# Power.net
KiCad netlist of a schematic drawn in Altium Designer
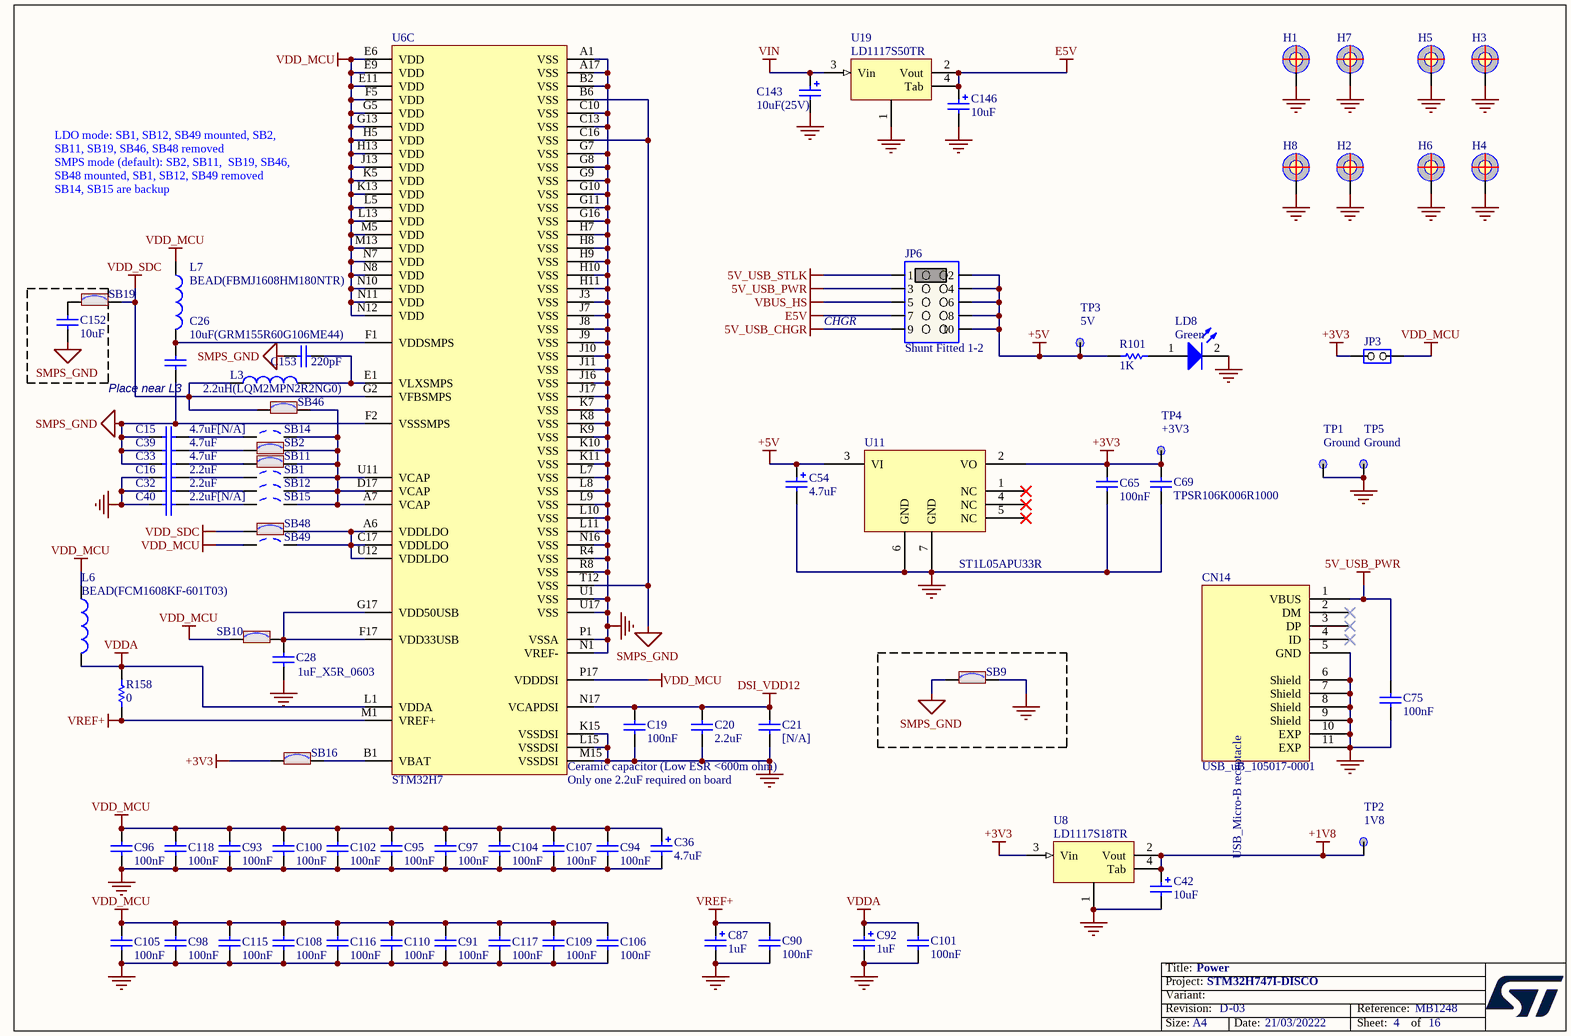
[diagram p0: Power.SchDoc]

(export (version "E")
  (design (tool "Eeschema 10.0.6"))
  (components
    (comp (ref "C15")
      (value "4.7uF[N/A]")
      (footprint "0402C")
      (description "Capacitor")
      (fields (field (name "PUBLISHER") "Altium Limited"))
      (libsource (lib "Miscellaneous Devices") (part "cap"))
    )
    (comp (ref "C16")
      (value "2.2uF")
      (footprint "0603C")
      (description "Capacitor")
      (fields (field (name "PUBLISHER") "Altium Limited"))
      (libsource (lib "Miscellaneous Devices") (part "Cap"))
    )
    (comp (ref "C19")
      (value "100nF")
      (footprint "0402C")
      (description "Capacitor")
      (fields (field (name "PUBLISHER") "Altium Limited"))
      (libsource (lib "Miscellaneous Devices") (part "CAP"))
    )
    (comp (ref "C20")
      (value "2.2uF")
      (footprint "0603C")
      (description "Capacitor")
      (fields (field (name "PUBLISHER") "Altium Limited"))
      (libsource (lib "Miscellaneous Devices") (part "CAP"))
    )
    (comp (ref "C21")
      (value "[N/A]")
      (footprint "1206C")
      (description "Capacitor")
      (fields (field (name "PUBLISHER") "Altium Limited"))
      (libsource (lib "Miscellaneous Devices") (part "cap"))
    )
    (comp (ref "C26")
      (value "10uF(GRM155R60G106ME44)")
      (footprint "0402C")
      (description "Capacitor")
      (fields (field (name "PUBLISHER") "Altium Limited"))
      (libsource (lib "Miscellaneous Devices") (part "Cap"))
    )
    (comp (ref "C28")
      (value "1uF_X5R_0603")
      (footprint "0603C")
      (description "0603  X5R 1礔")
      (fields (field (name "TOLERANCE") "10%"))
      (libsource (lib "MB963_1") (part "CAP SMD 0603  X5R 1礔 25V 10%"))
    )
    (comp (ref "C32")
      (value "2.2uF")
      (footprint "0603C")
      (description "Capacitor")
      (fields (field (name "PUBLISHER") "Altium Limited"))
      (libsource (lib "Miscellaneous Devices") (part "Cap"))
    )
    (comp (ref "C33")
      (value "4.7uF")
      (footprint "0402C")
      (description "Capacitor")
      (fields (field (name "PUBLISHER") "Altium Limited"))
      (libsource (lib "Miscellaneous Devices") (part "Cap"))
    )
    (comp (ref "C36")
      (value "4.7uF")
      (footprint "TAN-A")
      (description "Polarized Capacitor (Radial)")
      (fields (field (name "PUBLISHER") "Altium Limited"))
      (libsource (lib "Miscellaneous Devices") (part "Cap Pol1"))
    )
    (comp (ref "C39")
      (value "4.7uF")
      (footprint "0402C")
      (description "Capacitor")
      (fields (field (name "PUBLISHER") "Altium Limited"))
      (libsource (lib "Miscellaneous Devices") (part "Cap"))
    )
    (comp (ref "C40")
      (value "2.2uF[N/A]")
      (footprint "0603C")
      (description "Capacitor")
      (fields (field (name "PUBLISHER") "Altium Limited"))
      (libsource (lib "Miscellaneous Devices") (part "Cap"))
    )
    (comp (ref "C42")
      (value "10uF")
      (footprint "TAN-A")
      (description "Polarized Capacitor,10uF,10V,10%,typeA,VISHAY")
      (libsource (lib "MCD_TOOLS") (part "Cap_10uF_POL_10%_TANA"))
    )
    (comp (ref "C54")
      (value "4.7uF")
      (footprint "TAN-A")
      (description "Polarized Capacitor (Radial)")
      (fields (field (name "PUBLISHER") "Altium Limited"))
      (libsource (lib "*") (part "Cap Pol1"))
    )
    (comp (ref "C65")
      (value "100nF")
      (footprint "0603C")
      (description "Capacitor")
      (fields (field (name "PUBLISHER") "Altium Limited"))
      (libsource (lib "Miscellaneous Devices") (part "Cap"))
    )
    (comp (ref "C69")
      (value "TPSR106K006R1000")
      (footprint "0805C")
      (description "Capacitor")
      (libsource (lib "Miscellaneous Devices") (part "Cap"))
    )
    (comp (ref "C75")
      (value "100nF")
      (footprint "0402C")
      (description "Capacitor,20pF,50V,NPO,5%,0402")
      (fields
        (field (name "INTERNAL_PART_NUMBER") "MCD-00016")
        (field (name "MANUFACTURER_PART_NUMBER") "CC0402JRNPO9BN200")
        (field (name "PROVIDED_BY") "Subcon")
      )
      (libsource (lib "MCD_PARTS_database") (part "Capacitor"))
    )
    (comp (ref "C87")
      (value "1uF")
      (footprint "TAN-A")
      (description "Polarized Capacitor (Radial)")
      (fields (field (name "PUBLISHER") "Altium Limited"))
      (libsource (lib "Miscellaneous Devices") (part "Cap Pol1"))
    )
    (comp (ref "C90")
      (value "100nF")
      (footprint "0402C")
      (description "Capacitor")
      (fields (field (name "PUBLISHER") "Altium Limited"))
      (libsource (lib "Miscellaneous Devices") (part "Cap"))
    )
    (comp (ref "C91")
      (value "100nF")
      (footprint "0402C")
      (description "Capacitor")
      (fields (field (name "PUBLISHER") "Altium Limited"))
      (libsource (lib "Miscellaneous Devices") (part "CAP"))
    )
    (comp (ref "C92")
      (value "1uF")
      (footprint "TAN-A")
      (description "Polarized Capacitor (Radial)")
      (fields (field (name "PUBLISHER") "Altium Limited"))
      (libsource (lib "Miscellaneous Devices") (part "Cap Pol1"))
    )
    (comp (ref "C93")
      (value "100nF")
      (footprint "0402C")
      (description "Capacitor")
      (fields (field (name "PUBLISHER") "Altium Limited"))
      (libsource (lib "Miscellaneous Devices") (part "CAP"))
    )
    (comp (ref "C94")
      (value "100nF")
      (footprint "0402C")
      (description "Capacitor")
      (fields (field (name "PUBLISHER") "Altium Limited"))
      (libsource (lib "Miscellaneous Devices") (part "CAP"))
    )
    (comp (ref "C95")
      (value "100nF")
      (footprint "0402C")
      (description "Capacitor")
      (fields (field (name "PUBLISHER") "Altium Limited"))
      (libsource (lib "Miscellaneous Devices") (part "CAP"))
    )
    (comp (ref "C96")
      (value "100nF")
      (footprint "0402C")
      (description "Capacitor")
      (fields (field (name "PUBLISHER") "Altium Limited"))
      (libsource (lib "Miscellaneous Devices") (part "CAP"))
    )
    (comp (ref "C97")
      (value "100nF")
      (footprint "0402C")
      (description "Capacitor")
      (fields (field (name "PUBLISHER") "Altium Limited"))
      (libsource (lib "Miscellaneous Devices") (part "CAP"))
    )
    (comp (ref "C98")
      (value "100nF")
      (footprint "0402C")
      (description "Capacitor")
      (fields (field (name "PUBLISHER") "Altium Limited"))
      (libsource (lib "Miscellaneous Devices") (part "CAP"))
    )
    (comp (ref "C100")
      (value "100nF")
      (footprint "0402C")
      (description "Capacitor")
      (fields (field (name "PUBLISHER") "Altium Limited"))
      (libsource (lib "Miscellaneous Devices") (part "CAP"))
    )
    (comp (ref "C101")
      (value "100nF")
      (footprint "0402C")
      (description "Capacitor")
      (fields (field (name "PUBLISHER") "Altium Limited"))
      (libsource (lib "Miscellaneous Devices") (part "Cap"))
    )
    (comp (ref "C102")
      (value "100nF")
      (footprint "0402C")
      (description "Capacitor")
      (fields (field (name "PUBLISHER") "Altium Limited"))
      (libsource (lib "Miscellaneous Devices") (part "CAP"))
    )
    (comp (ref "C104")
      (value "100nF")
      (footprint "0402C")
      (description "Capacitor")
      (fields (field (name "PUBLISHER") "Altium Limited"))
      (libsource (lib "Miscellaneous Devices") (part "CAP"))
    )
    (comp (ref "C105")
      (value "100nF")
      (footprint "0402C")
      (description "Capacitor")
      (fields (field (name "PUBLISHER") "Altium Limited"))
      (libsource (lib "Miscellaneous Devices") (part "CAP"))
    )
    (comp (ref "C106")
      (value "100nF")
      (footprint "0402C")
      (description "Capacitor")
      (fields (field (name "PUBLISHER") "Altium Limited"))
      (libsource (lib "Miscellaneous Devices") (part "CAP"))
    )
    (comp (ref "C107")
      (value "100nF")
      (footprint "0402C")
      (description "Capacitor")
      (fields (field (name "PUBLISHER") "Altium Limited"))
      (libsource (lib "Miscellaneous Devices") (part "CAP"))
    )
    (comp (ref "C108")
      (value "100nF")
      (footprint "0402C")
      (description "Capacitor")
      (fields (field (name "PUBLISHER") "Altium Limited"))
      (libsource (lib "Miscellaneous Devices") (part "CAP"))
    )
    (comp (ref "C109")
      (value "100nF")
      (footprint "0402C")
      (description "Capacitor")
      (fields (field (name "PUBLISHER") "Altium Limited"))
      (libsource (lib "Miscellaneous Devices") (part "CAP"))
    )
    (comp (ref "C110")
      (value "100nF")
      (footprint "0402C")
      (description "Capacitor")
      (fields (field (name "PUBLISHER") "Altium Limited"))
      (libsource (lib "Miscellaneous Devices") (part "CAP"))
    )
    (comp (ref "C115")
      (value "100nF")
      (footprint "0402C")
      (description "Capacitor")
      (fields (field (name "PUBLISHER") "Altium Limited"))
      (libsource (lib "Miscellaneous Devices") (part "CAP"))
    )
    (comp (ref "C116")
      (value "100nF")
      (footprint "0402C")
      (description "Capacitor")
      (fields (field (name "PUBLISHER") "Altium Limited"))
      (libsource (lib "Miscellaneous Devices") (part "CAP"))
    )
    (comp (ref "C117")
      (value "100nF")
      (footprint "0402C")
      (description "Capacitor")
      (fields (field (name "PUBLISHER") "Altium Limited"))
      (libsource (lib "Miscellaneous Devices") (part "CAP"))
    )
    (comp (ref "C118")
      (value "100nF")
      (footprint "0402C")
      (description "Capacitor")
      (fields (field (name "PUBLISHER") "Altium Limited"))
      (libsource (lib "Miscellaneous Devices") (part "CAP"))
    )
    (comp (ref "C143")
      (value "10uF(25V)")
      (footprint "TAN-B")
      (description "Polarized Capacitor (Radial)")
      (fields (field (name "PUBLISHER") "Altium Limited"))
      (libsource (lib "Miscellaneous Devices") (part "Cap Pol1"))
    )
    (comp (ref "C146")
      (value "10uF")
      (footprint "TAN-A")
      (description "Polarized Capacitor,10uF,10V,10%,typeA,VISHAY")
      (libsource (lib "MCD_TOOLS") (part "Cap_10uF_POL_10%_TANA"))
    )
    (comp (ref "C152")
      (value "10uF")
      (footprint "0603C")
      (description "Capacitor")
      (fields (field (name "PUBLISHER") "Altium Limited"))
      (libsource (lib "Miscellaneous Devices") (part "Cap"))
    )
    (comp (ref "C153")
      (value "220pF")
      (footprint "0402C")
      (description "Capacitor")
      (fields (field (name "PUBLISHER") "Altium Limited"))
      (libsource (lib "Miscellaneous Devices") (part "Cap"))
    )
    (comp (ref "CN14")
      (value "USB_uB_105017-0001")
      (footprint "MICRO_USB_B_105017")
      (description "USB-MICRO-B, 0.65mm, RA, SMT, Bottom Mount,")
      (fields
        (field (name "INTERNAL_PART_NUMBER") "MCD-00028")
        (field (name "MANUFACTURER_PART_NUMBER") "1050170001")
        (field (name "PROVIDED_BY") "Subcon")
      )
      (libsource (lib "MCD_PARTS_database") (part "USB_uB_105017.0001"))
    )
    (comp (ref "H1")
      (value "POSITION HOLE C6D3R5")
      (footprint "HOLE_C7D3R5")
      (libsource (lib "MCD_TOOLS_MISCELLANEOUS") (part "POSITION HOLE C6D3R5"))
    )
    (comp (ref "H2")
      (value "POSITION HOLE C6D3R5")
      (footprint "HOLE_C7D3R5")
      (libsource (lib "MCD_TOOLS_MISCELLANEOUS") (part "POSITION HOLE C6D3R5"))
    )
    (comp (ref "H3")
      (value "POSITION HOLE C6D3R5")
      (footprint "HOLE_C9D4R5")
      (libsource (lib "MCD_TOOLS_MISCELLANEOUS") (part "POSITION HOLE C6D3R5"))
    )
    (comp (ref "H4")
      (value "POSITION HOLE C6D3R5")
      (footprint "HOLE_C9D4R5")
      (libsource (lib "MCD_TOOLS_MISCELLANEOUS") (part "POSITION HOLE C6D3R5"))
    )
    (comp (ref "H5")
      (value "POSITION HOLE C6D3R5")
      (footprint "HOLE_C9D4R5")
      (libsource (lib "MCD_TOOLS_MISCELLANEOUS") (part "POSITION HOLE C6D3R5"))
    )
    (comp (ref "H6")
      (value "POSITION HOLE C6D3R5")
      (footprint "HOLE_C9D4R5")
      (libsource (lib "MCD_TOOLS_MISCELLANEOUS") (part "POSITION HOLE C6D3R5"))
    )
    (comp (ref "H7")
      (value "POSITION HOLE C6D3R5")
      (footprint "HOLE_C7D3R5")
      (libsource (lib "MCD_TOOLS_MISCELLANEOUS") (part "POSITION HOLE C6D3R5"))
    )
    (comp (ref "H8")
      (value "POSITION HOLE C6D3R5")
      (footprint "HOLE_C7D3R5")
      (libsource (lib "MCD_TOOLS_MISCELLANEOUS") (part "POSITION HOLE C6D3R5"))
    )
    (comp (ref "JP3") (value "~") (footprint "SIP2") (libsource (lib "*") (part "JP2")))
    (comp (ref "JP6")
      (value "Shunt Fitted 1-2")
      (footprint "HDR_2X5_2R54")
      (description "Header, 5x2, 2,54mm, VR, TH, Height 5.84mm/2.54mm - Shunt Fitted 1-2")
      (fields
        (field (name "INTERNAL_PART_NUMBER") "MCD-01203")
        (field (name "MANUFACTURER_PART_NUMBER") "TSW-105-07-x-D")
        (field (name "PROVIDED_BY") "Subcon")
      )
      (libsource (lib "MCD_PARTS_database") (part "Jumper_Header 5x2 Fitted 1-2"))
    )
    (comp (ref "L3")
      (value "2.2uH(LQM2MPN2R2NG0)")
      (footprint "LSM2_VLS2016E_S")
      (description "Inductor")
      (fields (field (name "PUBLISHER") "Altium Limited"))
      (libsource (lib "Miscellaneous Devices") (part "Inductor"))
    )
    (comp (ref "L6")
      (value "BEAD(FCM1608KF-601T03)")
      (footprint "0603L")
      (description "Inductor")
      (fields (field (name "PUBLISHER") "Altium Limited"))
      (libsource (lib "Miscellaneous Devices") (part "Inductor"))
    )
    (comp (ref "L7")
      (value "BEAD(FBMJ1608HM180NTR)")
      (footprint "0603L")
      (description "Inductor")
      (fields (field (name "PUBLISHER") "Altium Limited"))
      (libsource (lib "Miscellaneous Devices") (part "Inductor"))
    )
    (comp (ref "LD8")
      (value "Green")
      (footprint "0603D")
      (description "Typical RED, GREEN, YELLOW, AMBER GaAs LED")
      (fields (field (name "PUBLISHER") "Altium Limited"))
      (libsource (lib "Miscellaneous Devices") (part "LED2"))
    )
    (comp (ref "R101")
      (value "1K")
      (footprint "0603R")
      (description "Resistor")
      (fields (field (name "PUBLISHER") "Altium Limited"))
      (libsource (lib "Miscellaneous Devices") (part "res1"))
    )
    (comp (ref "R158")
      (value "0")
      (footprint "0603R")
      (description "Resistor")
      (fields (field (name "PUBLISHER") "Altium Limited"))
      (libsource (lib "Miscellaneous Devices") (part "Res1"))
    )
    (comp (ref "SB1")
      (value "Solder Bridge OFF")
      (footprint "SB_0603")
      (libsource (lib "MCD_TOOLS") (part "SB_OFF"))
    )
    (comp (ref "SB2")
      (value "Solder Bridge ON")
      (footprint "SB_0603")
      (libsource (lib "MCD_TOOLS") (part "SB_ON"))
    )
    (comp (ref "SB9")
      (value "Solder Bridge ON")
      (footprint "SB_0603")
      (libsource (lib "MCD_TOOLS") (part "SB_ON"))
    )
    (comp (ref "SB10")
      (value "Solder Bridge ON")
      (footprint "SB_0603")
      (libsource (lib "MCD_TOOLS") (part "SB_ON"))
    )
    (comp (ref "SB11")
      (value "Solder Bridge ON")
      (footprint "SB_0603")
      (libsource (lib "MCD_TOOLS") (part "SB_ON"))
    )
    (comp (ref "SB12")
      (value "Solder Bridge OFF")
      (footprint "SB_0603")
      (libsource (lib "MCD_TOOLS") (part "SB_OFF"))
    )
    (comp (ref "SB14")
      (value "Solder Bridge OFF")
      (footprint "SB_0603")
      (libsource (lib "MCD_TOOLS") (part "SB_OFF"))
    )
    (comp (ref "SB15")
      (value "Solder Bridge OFF")
      (footprint "SB_0603")
      (libsource (lib "MCD_TOOLS") (part "SB_OFF"))
    )
    (comp (ref "SB16")
      (value "Solder Bridge ON")
      (footprint "SB_0603")
      (libsource (lib "MCD_TOOLS") (part "SB_ON"))
    )
    (comp (ref "SB19")
      (value "Solder Bridge ON")
      (footprint "SB_0603")
      (libsource (lib "MCD_TOOLS") (part "SB_ON"))
    )
    (comp (ref "SB46")
      (value "Solder Bridge ON")
      (footprint "SB_0603")
      (libsource (lib "MCD_TOOLS") (part "SB_ON"))
    )
    (comp (ref "SB48")
      (value "Solder Bridge ON")
      (footprint "SB_0603")
      (libsource (lib "MCD_TOOLS") (part "SB_ON"))
    )
    (comp (ref "SB49")
      (value "Solder Bridge OFF")
      (footprint "SB_0603")
      (libsource (lib "MCD_TOOLS") (part "SB_OFF"))
    )
    (comp (ref "TP1") (value "Ground") (footprint "TP_C40") (libsource (lib "*") (part "TP")))
    (comp (ref "TP2") (value "1V8") (footprint "TP_C40") (libsource (lib "*") (part "TP")))
    (comp (ref "TP3") (value "5V") (footprint "TP_C40") (libsource (lib "*") (part "TP")))
    (comp (ref "TP4") (value "+3V3") (footprint "TP_C40") (libsource (lib "*") (part "TP")))
    (comp (ref "TP5") (value "Ground") (footprint "TP_C40") (libsource (lib "*") (part "TP")))
    (comp (ref "U6")
      (value "STM32H7")
      (footprint "BGA265_0R8_14X14_SKT")
      (libsource (lib "MB1246") (part "STM32H7_TFBGA265"))
    )
    (comp (ref "U8") (value "LD1117S18TR") (footprint "SOT-223") (libsource (lib "mb1045") (part "LD1117")))
    (comp (ref "U11")
      (value "ST1L05APU33R")
      (footprint "DFN6_0R95_3X3")
      (libsource (lib "MB1248") (part "ST1L05A"))
    )
    (comp (ref "U19") (value "LD1117S50TR") (footprint "SOT-223") (libsource (lib "mb1045") (part "LD1117")))
  )
  (nets
    (net (code "1") (name "+1V8") (class "Default")
      (node (ref "C42") (pin "1") (pinfunction "1_1") (pintype "passive"))
      (node (ref "TP2") (pin "1") (pinfunction "1_1") (pintype "passive"))
      (node (ref "U8") (pin "2") (pinfunction "Vout_2") (pintype "power_in"))
      (node (ref "U8") (pin "4") (pinfunction "Tab_4") (pintype "power_in"))
    )
    (net (code "2") (name "+3V3") (class "Default")
      (node (ref "C65") (pin "1") (pinfunction "1_1") (pintype "passive"))
      (node (ref "C69") (pin "2") (pinfunction "2_2") (pintype "passive"))
      (node (ref "JP3") (pin "1") (pinfunction "COMMON_1") (pintype "passive"))
      (node (ref "SB16") (pin "1") (pinfunction "1_1") (pintype "passive"))
      (node (ref "TP4") (pin "1") (pinfunction "1_1") (pintype "passive"))
      (node (ref "U11") (pin "2") (pinfunction "VO_2") (pintype "passive"))
      (node (ref "U8") (pin "3") (pinfunction "Vin_3") (pintype "input"))
    )
    (net (code "3") (name "+5V") (class "Default")
      (node (ref "C54") (pin "1") (pinfunction "1_1") (pintype "passive"))
      (node (ref "JP6") (pin "10") (pinfunction "10_10") (pintype "passive"))
      (node (ref "JP6") (pin "2") (pinfunction "2_2") (pintype "passive"))
      (node (ref "JP6") (pin "4") (pinfunction "4_4") (pintype "passive"))
      (node (ref "JP6") (pin "6") (pinfunction "6_6") (pintype "passive"))
      (node (ref "JP6") (pin "8") (pinfunction "8_8") (pintype "passive"))
      (node (ref "R101") (pin "2") (pinfunction "2_2") (pintype "passive"))
      (node (ref "TP3") (pin "1") (pinfunction "1_1") (pintype "passive"))
      (node (ref "U11") (pin "3") (pinfunction "VI_3") (pintype "passive"))
    )
    (net (code "4") (name "5V_USB_CHGR") (class "Default")
      (node (ref "JP6") (pin "9") (pinfunction "9_9") (pintype "passive"))
    )
    (net (code "5") (name "5V_USB_PWR") (class "Default")
      (node (ref "C75") (pin "2") (pinfunction "2_2") (pintype "passive"))
      (node (ref "CN14") (pin "1") (pinfunction "VBUS_1") (pintype "passive"))
      (node (ref "JP6") (pin "3") (pinfunction "3_3") (pintype "passive"))
    )
    (net (code "6") (name "5V_USB_STLK") (class "Default")
      (node (ref "JP6") (pin "1") (pinfunction "1_1") (pintype "passive"))
    )
    (net (code "7") (name "DSI_VDD12") (class "Default")
      (node (ref "C19") (pin "1") (pinfunction "1_1") (pintype "passive"))
      (node (ref "C20") (pin "1") (pinfunction "1_1") (pintype "passive"))
      (node (ref "C21") (pin "2") (pinfunction "2_2") (pintype "passive"))
      (node (ref "U6") (pin "N17") (pinfunction "VCAPDSI_N17") (pintype "passive"))
    )
    (net (code "8") (name "E5V") (class "Default")
      (node (ref "C146") (pin "1") (pinfunction "1_1") (pintype "passive"))
      (node (ref "JP6") (pin "7") (pinfunction "7_7") (pintype "passive"))
      (node (ref "U19") (pin "2") (pinfunction "Vout_2") (pintype "power_in"))
      (node (ref "U19") (pin "4") (pinfunction "Tab_4") (pintype "power_in"))
    )
    (net (code "9") (name "GND") (class "Default")
      (node (ref "C100") (pin "2") (pinfunction "2_2") (pintype "passive"))
      (node (ref "C101") (pin "1") (pinfunction "1_1") (pintype "passive"))
      (node (ref "C102") (pin "2") (pinfunction "2_2") (pintype "passive"))
      (node (ref "C104") (pin "2") (pinfunction "2_2") (pintype "passive"))
      (node (ref "C105") (pin "2") (pinfunction "2_2") (pintype "passive"))
      (node (ref "C106") (pin "2") (pinfunction "2_2") (pintype "passive"))
      (node (ref "C107") (pin "2") (pinfunction "2_2") (pintype "passive"))
      (node (ref "C108") (pin "2") (pinfunction "2_2") (pintype "passive"))
      (node (ref "C109") (pin "2") (pinfunction "2_2") (pintype "passive"))
      (node (ref "C110") (pin "2") (pinfunction "2_2") (pintype "passive"))
      (node (ref "C115") (pin "2") (pinfunction "2_2") (pintype "passive"))
      (node (ref "C116") (pin "2") (pinfunction "2_2") (pintype "passive"))
      (node (ref "C117") (pin "2") (pinfunction "2_2") (pintype "passive"))
      (node (ref "C118") (pin "2") (pinfunction "2_2") (pintype "passive"))
      (node (ref "C143") (pin "2") (pinfunction "2_2") (pintype "passive"))
      (node (ref "C146") (pin "2") (pinfunction "2_2") (pintype "passive"))
      (node (ref "C16") (pin "1") (pinfunction "1_1") (pintype "passive"))
      (node (ref "C19") (pin "2") (pinfunction "2_2") (pintype "passive"))
      (node (ref "C20") (pin "2") (pinfunction "2_2") (pintype "passive"))
      (node (ref "C21") (pin "1") (pinfunction "1_1") (pintype "passive"))
      (node (ref "C28") (pin "1") (pinfunction "1_1") (pintype "passive"))
      (node (ref "C32") (pin "1") (pinfunction "1_1") (pintype "passive"))
      (node (ref "C36") (pin "2") (pinfunction "2_2") (pintype "passive"))
      (node (ref "C40") (pin "1") (pinfunction "1_1") (pintype "passive"))
      (node (ref "C42") (pin "2") (pinfunction "2_2") (pintype "passive"))
      (node (ref "C54") (pin "2") (pinfunction "2_2") (pintype "passive"))
      (node (ref "C65") (pin "2") (pinfunction "2_2") (pintype "passive"))
      (node (ref "C69") (pin "1") (pinfunction "1_1") (pintype "passive"))
      (node (ref "C75") (pin "1") (pinfunction "1_1") (pintype "passive"))
      (node (ref "C87") (pin "2") (pinfunction "2_2") (pintype "passive"))
      (node (ref "C90") (pin "1") (pinfunction "1_1") (pintype "passive"))
      (node (ref "C91") (pin "2") (pinfunction "2_2") (pintype "passive"))
      (node (ref "C92") (pin "2") (pinfunction "2_2") (pintype "passive"))
      (node (ref "C93") (pin "2") (pinfunction "2_2") (pintype "passive"))
      (node (ref "C94") (pin "2") (pinfunction "2_2") (pintype "passive"))
      (node (ref "C95") (pin "2") (pinfunction "2_2") (pintype "passive"))
      (node (ref "C96") (pin "2") (pinfunction "2_2") (pintype "passive"))
      (node (ref "C97") (pin "2") (pinfunction "2_2") (pintype "passive"))
      (node (ref "C98") (pin "2") (pinfunction "2_2") (pintype "passive"))
      (node (ref "CN14") (pin "10") (pinfunction "EXP_10") (pintype "passive"))
      (node (ref "CN14") (pin "11") (pinfunction "EXP_11") (pintype "passive"))
      (node (ref "CN14") (pin "5") (pinfunction "GND_5") (pintype "passive"))
      (node (ref "CN14") (pin "6") (pinfunction "Shield_6") (pintype "passive"))
      (node (ref "CN14") (pin "7") (pinfunction "Shield_7") (pintype "passive"))
      (node (ref "CN14") (pin "8") (pinfunction "Shield_8") (pintype "passive"))
      (node (ref "CN14") (pin "9") (pinfunction "Shield_9") (pintype "passive"))
      (node (ref "H1") (pin "1") (pinfunction "1_1") (pintype "passive"))
      (node (ref "H2") (pin "1") (pinfunction "1_1") (pintype "passive"))
      (node (ref "H3") (pin "1") (pinfunction "1_1") (pintype "passive"))
      (node (ref "H4") (pin "1") (pinfunction "1_1") (pintype "passive"))
      (node (ref "H5") (pin "1") (pinfunction "1_1") (pintype "passive"))
      (node (ref "H6") (pin "1") (pinfunction "1_1") (pintype "passive"))
      (node (ref "H7") (pin "1") (pinfunction "1_1") (pintype "passive"))
      (node (ref "H8") (pin "1") (pinfunction "1_1") (pintype "passive"))
      (node (ref "LD8") (pin "2") (pinfunction "K_2") (pintype "passive"))
      (node (ref "SB9") (pin "2") (pinfunction "2_2") (pintype "passive"))
      (node (ref "TP1") (pin "1") (pinfunction "1_1") (pintype "passive"))
      (node (ref "TP5") (pin "1") (pinfunction "1_1") (pintype "passive"))
      (node (ref "U11") (pin "6") (pinfunction "GND_6") (pintype "passive"))
      (node (ref "U11") (pin "7") (pinfunction "GND_7") (pintype "passive"))
      (node (ref "U19") (pin "1") (pintype "passive"))
      (node (ref "U6") (pin "A1") (pinfunction "VSS_A1") (pintype "passive"))
      (node (ref "U6") (pin "A17") (pinfunction "VSS_A17") (pintype "passive"))
      (node (ref "U6") (pin "B2") (pinfunction "VSS_B2") (pintype "passive"))
      (node (ref "U6") (pin "C10") (pinfunction "VSS_C10") (pintype "passive"))
      (node (ref "U6") (pin "C13") (pinfunction "VSS_C13") (pintype "passive"))
      (node (ref "U6") (pin "G10") (pinfunction "VSS_G10") (pintype "passive"))
      (node (ref "U6") (pin "G11") (pinfunction "VSS_G11") (pintype "passive"))
      (node (ref "U6") (pin "G16") (pinfunction "VSS_G16") (pintype "passive"))
      (node (ref "U6") (pin "G7") (pinfunction "VSS_G7") (pintype "passive"))
      (node (ref "U6") (pin "G8") (pinfunction "VSS_G8") (pintype "passive"))
      (node (ref "U6") (pin "G9") (pinfunction "VSS_G9") (pintype "passive"))
      (node (ref "U6") (pin "H10") (pinfunction "VSS_H10") (pintype "passive"))
      (node (ref "U6") (pin "H11") (pinfunction "VSS_H11") (pintype "passive"))
      (node (ref "U6") (pin "H7") (pinfunction "VSS_H7") (pintype "passive"))
      (node (ref "U6") (pin "H8") (pinfunction "VSS_H8") (pintype "passive"))
      (node (ref "U6") (pin "H9") (pinfunction "VSS_H9") (pintype "passive"))
      (node (ref "U6") (pin "J10") (pinfunction "VSS_J10") (pintype "passive"))
      (node (ref "U6") (pin "J11") (pinfunction "VSS_J11") (pintype "passive"))
      (node (ref "U6") (pin "J16") (pinfunction "VSS_J16") (pintype "passive"))
      (node (ref "U6") (pin "J17") (pinfunction "VSS_J17") (pintype "passive"))
      (node (ref "U6") (pin "J3") (pinfunction "VSS_J3") (pintype "passive"))
      (node (ref "U6") (pin "J7") (pinfunction "VSS_J7") (pintype "passive"))
      (node (ref "U6") (pin "J8") (pinfunction "VSS_J8") (pintype "passive"))
      (node (ref "U6") (pin "J9") (pinfunction "VSS_J9") (pintype "passive"))
      (node (ref "U6") (pin "K10") (pinfunction "VSS_K10") (pintype "passive"))
      (node (ref "U6") (pin "K11") (pinfunction "VSS_K11") (pintype "passive"))
      (node (ref "U6") (pin "K15") (pinfunction "VSSDSI_K15") (pintype "passive"))
      (node (ref "U6") (pin "K7") (pinfunction "VSS_K7") (pintype "passive"))
      (node (ref "U6") (pin "K8") (pinfunction "VSS_K8") (pintype "passive"))
      (node (ref "U6") (pin "K9") (pinfunction "VSS_K9") (pintype "passive"))
      (node (ref "U6") (pin "L10") (pinfunction "VSS_L10") (pintype "passive"))
      (node (ref "U6") (pin "L11") (pinfunction "VSS_L11") (pintype "passive"))
      (node (ref "U6") (pin "L15") (pinfunction "VSSDSI_L15") (pintype "passive"))
      (node (ref "U6") (pin "L7") (pinfunction "VSS_L7") (pintype "passive"))
      (node (ref "U6") (pin "L8") (pinfunction "VSS_L8") (pintype "passive"))
      (node (ref "U6") (pin "L9") (pinfunction "VSS_L9") (pintype "passive"))
      (node (ref "U6") (pin "M15") (pinfunction "VSSDSI_M15") (pintype "passive"))
      (node (ref "U6") (pin "N1") (pinfunction "VREF-_N1") (pintype "passive"))
      (node (ref "U6") (pin "N16") (pinfunction "VSS_N16") (pintype "passive"))
      (node (ref "U6") (pin "P1") (pinfunction "VSSA_P1") (pintype "passive"))
      (node (ref "U6") (pin "R4") (pinfunction "VSS_R4") (pintype "passive"))
      (node (ref "U6") (pin "R8") (pinfunction "VSS_R8") (pintype "passive"))
      (node (ref "U6") (pin "U1") (pinfunction "VSS_U1") (pintype "passive"))
      (node (ref "U6") (pin "U17") (pinfunction "VSS_U17") (pintype "passive"))
      (node (ref "U8") (pin "1") (pintype "passive"))
    )
    (net (code "10") (name "Net-(C15-Pad2)") (class "Default")
      (node (ref "C15") (pin "2") (pinfunction "2_2") (pintype "passive"))
      (node (ref "SB14") (pin "1") (pinfunction "1_1") (pintype "passive"))
    )
    (net (code "11") (name "Net-(C16-Pad2)") (class "Default")
      (node (ref "C16") (pin "2") (pinfunction "2_2") (pintype "passive"))
      (node (ref "SB1") (pin "1") (pinfunction "1_1") (pintype "passive"))
    )
    (net (code "12") (name "Net-(C32-Pad2)") (class "Default")
      (node (ref "C32") (pin "2") (pinfunction "2_2") (pintype "passive"))
      (node (ref "SB12") (pin "1") (pinfunction "1_1") (pintype "passive"))
    )
    (net (code "13") (name "Net-(C33-Pad2)") (class "Default")
      (node (ref "C33") (pin "2") (pinfunction "2_2") (pintype "passive"))
      (node (ref "SB11") (pin "1") (pinfunction "1_1") (pintype "passive"))
    )
    (net (code "14") (name "Net-(C39-Pad2)") (class "Default")
      (node (ref "C39") (pin "2") (pinfunction "2_2") (pintype "passive"))
      (node (ref "SB2") (pin "1") (pinfunction "1_1") (pintype "passive"))
    )
    (net (code "15") (name "Net-(C40-Pad2)") (class "Default")
      (node (ref "C40") (pin "2") (pinfunction "2_2") (pintype "passive"))
      (node (ref "SB15") (pin "1") (pinfunction "1_1") (pintype "passive"))
    )
    (net (code "16") (name "Net-(C152-Pad2)") (class "Default")
      (node (ref "C152") (pin "2") (pinfunction "2_2") (pintype "passive"))
      (node (ref "SB19") (pin "1") (pinfunction "1_1") (pintype "passive"))
    )
    (net (code "17") (name "Net-(LD8-A)") (class "Default")
      (node (ref "LD8") (pin "1") (pinfunction "A_1") (pintype "passive"))
      (node (ref "R101") (pin "1") (pinfunction "1_1") (pintype "passive"))
    )
    (net (code "18") (name "Net-(SB1-Pad2)") (class "Default")
      (node (ref "SB1") (pin "2") (pinfunction "2_2") (pintype "passive"))
      (node (ref "SB11") (pin "2") (pinfunction "2_2") (pintype "passive"))
      (node (ref "SB12") (pin "2") (pinfunction "2_2") (pintype "passive"))
      (node (ref "SB14") (pin "2") (pinfunction "2_2") (pintype "passive"))
      (node (ref "SB15") (pin "2") (pinfunction "2_2") (pintype "passive"))
      (node (ref "SB2") (pin "2") (pinfunction "2_2") (pintype "passive"))
      (node (ref "SB46") (pin "2") (pinfunction "2_2") (pintype "passive"))
      (node (ref "U6") (pin "A7") (pinfunction "VCAP_A7") (pintype "passive"))
      (node (ref "U6") (pin "D17") (pinfunction "VCAP_D17") (pintype "passive"))
      (node (ref "U6") (pin "U11") (pinfunction "VCAP_U11") (pintype "passive"))
    )
    (net (code "19") (name "Net-(SB48-Pad2)") (class "Default")
      (node (ref "SB48") (pin "2") (pinfunction "2_2") (pintype "passive"))
      (node (ref "SB49") (pin "2") (pinfunction "2_2") (pintype "passive"))
      (node (ref "U6") (pin "A6") (pinfunction "VDDLDO_A6") (pintype "passive"))
      (node (ref "U6") (pin "C17") (pinfunction "VDDLDO_C17") (pintype "passive"))
      (node (ref "U6") (pin "U12") (pinfunction "VDDLDO_U12") (pintype "passive"))
    )
    (net (code "20") (name "Net-(U6C-VBAT)") (class "Default")
      (node (ref "SB16") (pin "2") (pinfunction "2_2") (pintype "passive"))
      (node (ref "U6") (pin "B1") (pinfunction "VBAT_B1") (pintype "passive"))
    )
    (net (code "21") (name "Net-(U6C-VDD33USB)") (class "Default")
      (node (ref "C28") (pin "2") (pinfunction "2_2") (pintype "passive"))
      (node (ref "SB10") (pin "2") (pinfunction "2_2") (pintype "passive"))
      (node (ref "U6") (pin "F17") (pinfunction "VDD33USB_F17") (pintype "passive"))
      (node (ref "U6") (pin "G17") (pinfunction "VDD50USB_G17") (pintype "passive"))
    )
    (net (code "22") (name "Net-(U6C-VDDSMPS)") (class "Default")
      (node (ref "C26") (pin "2") (pinfunction "2_2") (pintype "passive"))
      (node (ref "L7") (pin "2") (pinfunction "2_2") (pintype "passive"))
      (node (ref "U6") (pin "F1") (pinfunction "VDDSMPS_F1") (pintype "passive"))
    )
    (net (code "23") (name "Net-(U6C-VLXSMPS)") (class "Default")
      (node (ref "C153") (pin "1") (pinfunction "1_1") (pintype "passive"))
      (node (ref "L3") (pin "2") (pinfunction "2_2") (pintype "passive"))
      (node (ref "U6") (pin "E1") (pinfunction "VLXSMPS_E1") (pintype "passive"))
    )
    (net (code "24") (name "SMPS_GND") (class "Default")
      (node (ref "C15") (pin "1") (pinfunction "1_1") (pintype "passive"))
      (node (ref "C152") (pin "1") (pinfunction "1_1") (pintype "passive"))
      (node (ref "C153") (pin "2") (pinfunction "2_2") (pintype "passive"))
      (node (ref "C26") (pin "1") (pinfunction "1_1") (pintype "passive"))
      (node (ref "C33") (pin "1") (pinfunction "1_1") (pintype "passive"))
      (node (ref "C39") (pin "1") (pinfunction "1_1") (pintype "passive"))
      (node (ref "SB9") (pin "1") (pinfunction "1_1") (pintype "passive"))
      (node (ref "U6") (pin "B6") (pinfunction "VSS_B6") (pintype "passive"))
      (node (ref "U6") (pin "C16") (pinfunction "VSS_C16") (pintype "passive"))
      (node (ref "U6") (pin "F2") (pinfunction "VSSSMPS_F2") (pintype "passive"))
      (node (ref "U6") (pin "T12") (pinfunction "VSS_T12") (pintype "passive"))
    )
    (net (code "25") (name "VBUS_HS") (class "Default")
      (node (ref "JP6") (pin "5") (pinfunction "5_5") (pintype "passive"))
    )
    (net (code "26") (name "VDDA") (class "Default")
      (node (ref "C101") (pin "2") (pinfunction "2_2") (pintype "passive"))
      (node (ref "C92") (pin "1") (pinfunction "1_1") (pintype "passive"))
      (node (ref "L6") (pin "2") (pinfunction "2_2") (pintype "passive"))
      (node (ref "R158") (pin "1") (pinfunction "1_1") (pintype "passive"))
      (node (ref "U6") (pin "L1") (pinfunction "VDDA_L1") (pintype "passive"))
    )
    (net (code "27") (name "VDD_MCU") (class "Default")
      (node (ref "C100") (pin "1") (pinfunction "1_1") (pintype "passive"))
      (node (ref "C102") (pin "1") (pinfunction "1_1") (pintype "passive"))
      (node (ref "C104") (pin "1") (pinfunction "1_1") (pintype "passive"))
      (node (ref "C105") (pin "1") (pinfunction "1_1") (pintype "passive"))
      (node (ref "C106") (pin "1") (pinfunction "1_1") (pintype "passive"))
      (node (ref "C107") (pin "1") (pinfunction "1_1") (pintype "passive"))
      (node (ref "C108") (pin "1") (pinfunction "1_1") (pintype "passive"))
      (node (ref "C109") (pin "1") (pinfunction "1_1") (pintype "passive"))
      (node (ref "C110") (pin "1") (pinfunction "1_1") (pintype "passive"))
      (node (ref "C115") (pin "1") (pinfunction "1_1") (pintype "passive"))
      (node (ref "C116") (pin "1") (pinfunction "1_1") (pintype "passive"))
      (node (ref "C117") (pin "1") (pinfunction "1_1") (pintype "passive"))
      (node (ref "C118") (pin "1") (pinfunction "1_1") (pintype "passive"))
      (node (ref "C36") (pin "1") (pinfunction "1_1") (pintype "passive"))
      (node (ref "C91") (pin "1") (pinfunction "1_1") (pintype "passive"))
      (node (ref "C93") (pin "1") (pinfunction "1_1") (pintype "passive"))
      (node (ref "C94") (pin "1") (pinfunction "1_1") (pintype "passive"))
      (node (ref "C95") (pin "1") (pinfunction "1_1") (pintype "passive"))
      (node (ref "C96") (pin "1") (pinfunction "1_1") (pintype "passive"))
      (node (ref "C97") (pin "1") (pinfunction "1_1") (pintype "passive"))
      (node (ref "C98") (pin "1") (pinfunction "1_1") (pintype "passive"))
      (node (ref "JP3") (pin "2") (pinfunction "NO_2") (pintype "passive"))
      (node (ref "L6") (pin "1") (pinfunction "1_1") (pintype "passive"))
      (node (ref "L7") (pin "1") (pinfunction "1_1") (pintype "passive"))
      (node (ref "SB10") (pin "1") (pinfunction "1_1") (pintype "passive"))
      (node (ref "SB49") (pin "1") (pinfunction "1_1") (pintype "passive"))
      (node (ref "U6") (pin "E11") (pinfunction "VDD_E11") (pintype "passive"))
      (node (ref "U6") (pin "E6") (pinfunction "VDD_E6") (pintype "passive"))
      (node (ref "U6") (pin "E9") (pinfunction "VDD_E9") (pintype "passive"))
      (node (ref "U6") (pin "F5") (pinfunction "VDD_F5") (pintype "passive"))
      (node (ref "U6") (pin "G13") (pinfunction "VDD_G13") (pintype "passive"))
      (node (ref "U6") (pin "G5") (pinfunction "VDD_G5") (pintype "passive"))
      (node (ref "U6") (pin "H13") (pinfunction "VDD_H13") (pintype "passive"))
      (node (ref "U6") (pin "H5") (pinfunction "VDD_H5") (pintype "passive"))
      (node (ref "U6") (pin "J13") (pinfunction "VDD_J13") (pintype "passive"))
      (node (ref "U6") (pin "K13") (pinfunction "VDD_K13") (pintype "passive"))
      (node (ref "U6") (pin "K5") (pinfunction "VDD_K5") (pintype "passive"))
      (node (ref "U6") (pin "L13") (pinfunction "VDD_L13") (pintype "passive"))
      (node (ref "U6") (pin "L5") (pinfunction "VDD_L5") (pintype "passive"))
      (node (ref "U6") (pin "M13") (pinfunction "VDD_M13") (pintype "passive"))
      (node (ref "U6") (pin "M5") (pinfunction "VDD_M5") (pintype "passive"))
      (node (ref "U6") (pin "N10") (pinfunction "VDD_N10") (pintype "passive"))
      (node (ref "U6") (pin "N11") (pinfunction "VDD_N11") (pintype "passive"))
      (node (ref "U6") (pin "N12") (pinfunction "VDD_N12") (pintype "passive"))
      (node (ref "U6") (pin "N7") (pinfunction "VDD_N7") (pintype "passive"))
      (node (ref "U6") (pin "N8") (pinfunction "VDD_N8") (pintype "passive"))
      (node (ref "U6") (pin "P17") (pinfunction "VDDDSI_P17") (pintype "passive"))
    )
    (net (code "28") (name "VDD_SDC") (class "Default")
      (node (ref "L3") (pin "1") (pinfunction "1_1") (pintype "passive"))
      (node (ref "SB19") (pin "2") (pinfunction "2_2") (pintype "passive"))
      (node (ref "SB46") (pin "1") (pinfunction "1_1") (pintype "passive"))
      (node (ref "SB48") (pin "1") (pinfunction "1_1") (pintype "passive"))
      (node (ref "U6") (pin "G2") (pinfunction "VFBSMPS_G2") (pintype "passive"))
    )
    (net (code "29") (name "VIN") (class "Default")
      (node (ref "C143") (pin "1") (pinfunction "1_1") (pintype "passive"))
      (node (ref "U19") (pin "3") (pinfunction "Vin_3") (pintype "input"))
    )
    (net (code "30") (name "VREF+") (class "Default")
      (node (ref "C87") (pin "1") (pinfunction "1_1") (pintype "passive"))
      (node (ref "C90") (pin "2") (pinfunction "2_2") (pintype "passive"))
      (node (ref "R158") (pin "2") (pinfunction "2_2") (pintype "passive"))
      (node (ref "U6") (pin "M1") (pinfunction "VREF+_M1") (pintype "passive"))
    )
    (net (code "31") (name "unconnected-(CN14-DM-Pad2)") (class "Default")
      (node (ref "CN14") (pin "2") (pinfunction "DM_2") (pintype "passive+no_connect"))
    )
    (net (code "32") (name "unconnected-(CN14-DP-Pad3)") (class "Default")
      (node (ref "CN14") (pin "3") (pinfunction "DP_3") (pintype "passive+no_connect"))
    )
    (net (code "33") (name "unconnected-(CN14-ID-Pad4)") (class "Default")
      (node (ref "CN14") (pin "4") (pinfunction "ID_4") (pintype "passive+no_connect"))
    )
    (net (code "34") (name "unconnected-(U11-NC-Pad1)") (class "Default")
      (node (ref "U11") (pin "1") (pinfunction "NC_1") (pintype "passive+no_connect"))
    )
    (net (code "35") (name "unconnected-(U11-NC-Pad4)") (class "Default")
      (node (ref "U11") (pin "4") (pinfunction "NC_4") (pintype "passive+no_connect"))
    )
    (net (code "36") (name "unconnected-(U11-NC-Pad5)") (class "Default")
      (node (ref "U11") (pin "5") (pinfunction "NC_5") (pintype "passive+no_connect"))
    )
  )
)
